# Sheet1.net
KiCad netlist of a schematic drawn in Altium Designer
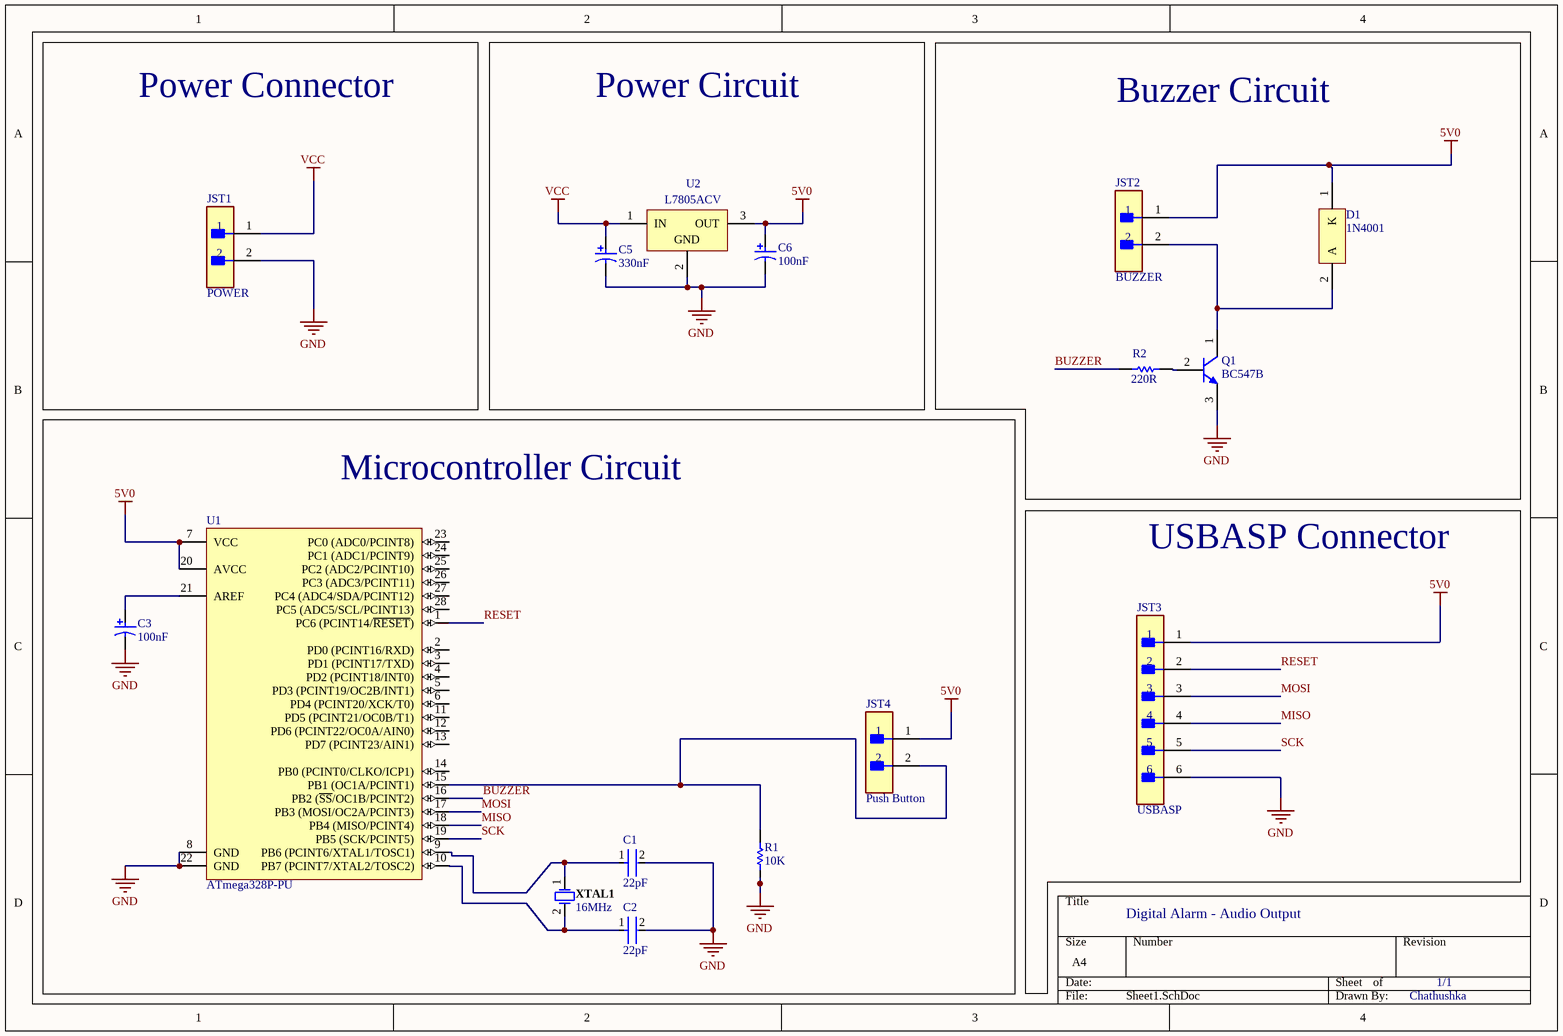
[diagram p0: Sheet1.SchDoc]

(export (version "E")
  (design (tool "Eeschema 10.0.6"))
  (components
    (comp (ref "C1")
      (value "22pF")
      (footprint "FP-RCE0K1-MFG")
      (description "Cap Ceramic 22pF 50V C0G ±5% Radial 5mm +125°C Automotive Bulk")
      (fields (field (name "TOLERANCE") "5%"))
      (libsource (lib "Altium Content Vault") (part "b4654b650e69147ec39a6b967a45e02"))
    )
    (comp (ref "C2")
      (value "22pF")
      (footprint "FP-RCE0K1-MFG")
      (description "Cap Ceramic 22pF 50V C0G ±5% Radial 5mm +125°C Automotive Bulk")
      (fields (field (name "TOLERANCE") "5%"))
      (libsource (lib "Altium Content Vault") (part "b4654b650e69147ec39a6b967a45e02"))
    )
    (comp (ref "C3")
      (value "100nF")
      (footprint "CAPPR65-350-1150X800X1250")
      (description "Aluminum Electrolytic Capacitor, 100 uF, +/- 20%, 50 V, -40 to 85 degC, 2-Pin THD, RoHS, Bulk")
      (fields (field (name "MANUFACTURER") "Panasonic") (field (name "VOLTAGE") "50V"))
      (libsource (lib "Altium Content Vault") (part "CAP-P-2"))
    )
    (comp (ref "C5")
      (value "330nF")
      (footprint "CAPPR65-350-1150X800X1250")
      (description "Aluminum Electrolytic Capacitor, 100 nF, +/- 20%, 50 V, -40 to 85 degC, 2-Pin THD, RoHS, Bulk")
      (fields (field (name "MANUFACTURER") "Panasonic") (field (name "VOLTAGE") "50V"))
      (libsource (lib "Altium Content Vault") (part "CAP-P-2"))
    )
    (comp (ref "C6")
      (value "100nF")
      (footprint "CAPPR65-350-1150X800X1250")
      (description "Aluminum Electrolytic Capacitor, 100 nF, +/- 20%, 50 V, -40 to 85 degC, 2-Pin THD, RoHS, Bulk")
      (fields (field (name "MANUFACTURER") "Panasonic") (field (name "VOLTAGE") "50V"))
      (libsource (lib "Altium Content Vault") (part "CAP-P-2"))
    )
    (comp (ref "D1")
      (value "1N4001")
      (footprint "ONSC-AXIAL_LEAD-2-59-10_P")
      (description "Standard Recovery Rectifier, 2-Pin Axial_Lead, Pb-Free, Bulk Bag")
      (fields (field (name "MANUFACTURER") "On Semiconductor"))
      (libsource (lib "Altium Content Vault") (part "ONSC-D-K1A2-2_A"))
    )
    (comp (ref "JST1")
      (value "POWER")
      (footprint "FP-B2B-XH-A_LF_SN-MFG")
      (description "CONN HEADER VERT 2POS 2.5MM")
      (libsource (lib "Altium Content Vault") (part "3bc925449376181038e59eaffc5286c"))
    )
    (comp (ref "JST2")
      (value "BUZZER")
      (footprint "FP-B2B-XH-A_LF_SN-MFG")
      (description "CONN HEADER VERT 2POS 2.5MM")
      (libsource (lib "Altium Content Vault") (part "3bc925449376181038e59eaffc5286c"))
    )
    (comp (ref "JST3")
      (value "USBASP")
      (footprint "FP-M30-6100646-MFG")
      (description "CONN HEADER VERT 6POS 1.25MM")
      (fields (field (name "MANUFACTURER PART NUMBER") "M30-6100646") (field (name "MANUFACTURER") "Harwin"))
      (libsource (lib "Altium Content Vault") (part "f2cb566baf1c37ab5a3b8e90bbeafd6"))
    )
    (comp (ref "JST4")
      (value "Push Button")
      (footprint "FP-B2B-XH-A_LF_SN-MFG")
      (description "CONN HEADER VERT 2POS 2.5MM")
      (libsource (lib "Altium Content Vault") (part "3bc925449376181038e59eaffc5286c"))
    )
    (comp (ref "Q1")
      (value "BC547B")
      (footprint "ONSC-TO-92-3-29-11")
      (description "Amplifier Transistor, NPN Silicon, 3-Pin TO-92, Bulk Box")
      (fields (field (name "MANUFACTURER") "On Semiconductor"))
      (libsource (lib "Altium Content Vault") (part "ONSC-NPN-C1B2E3-3"))
    )
    (comp (ref "R1")
      (value "10K")
      (footprint "OMTE-RES7X2.5-2")
      (fields
        (field (name "TOLERANCE") "±5%")
        (field (name "PARTNUMBER") "OD103JE")
        (field (name "MANUFACTURER") "Ohmite")
      )
      (libsource (lib "Altium Content Vault") (part "RES-2"))
    )
    (comp (ref "R2")
      (value "220R")
      (footprint "OMTE-RES7X2.5-2")
      (fields
        (field (name "TOLERANCE") "±5%")
        (field (name "PARTNUMBER") "OD103JE")
        (field (name "MANUFACTURER") "Ohmite")
      )
      (libsource (lib "Altium Content Vault") (part "RES-2"))
    )
    (comp (ref "U1")
      (value "ATmega328P-PU")
      (footprint "28P3")
      (libsource (lib "Altium Content Vault") (part "MC-8B-ATM48-IL28"))
    )
    (comp (ref "U2")
      (value "L7805ACV")
      (footprint "TO220")
      (description "Positive Voltage Regulator, 5V, 3-Pin TO-220")
      (libsource (lib "Altium Content Vault") (part "PM-REG-L4940-SIL3"))
    )
    (comp (ref "XTAL1")
      (value "16MHz")
      (footprint "FOX-FOXSLF160-20")
      (description "Resistance Weld Thru-Hole Crystal, 16 MHz, -20 to 70 degC, 2-Pin THD, RoHS, Bulk")
      (fields (field (name "TOLERANCE") "1%"))
      (libsource (lib "Altium Content Vault") (part "XTAL-1-2-2"))
    )
  )
  (nets
    (net (code "1") (name "/BUZZER") (class "Default")
      (node (ref "R2") (pin "1") (pinfunction "1_1") (pintype "passive"))
      (node (ref "U1") (pin "16") (pinfunction "PB2_(~{SS}/OC1B/PCINT2)_16") (pintype "bidirectional"))
    )
    (net (code "2") (name "/MISO") (class "Default")
      (node (ref "JST3") (pin "4") (pinfunction "4_4") (pintype "passive"))
      (node (ref "U1") (pin "18") (pinfunction "PB4_(MISO/PCINT4)_18") (pintype "bidirectional"))
    )
    (net (code "3") (name "/MOSI") (class "Default")
      (node (ref "JST3") (pin "3") (pinfunction "3_3") (pintype "passive"))
      (node (ref "U1") (pin "17") (pinfunction "PB3_(MOSI/OC2A/PCINT3)_17") (pintype "bidirectional"))
    )
    (net (code "4") (name "/RESET") (class "Default")
      (node (ref "JST3") (pin "2") (pinfunction "2_2") (pintype "passive"))
      (node (ref "U1") (pin "1") (pinfunction "PC6_(PCINT14/~{RESET})_1") (pintype "bidirectional"))
    )
    (net (code "5") (name "/SCK") (class "Default")
      (node (ref "JST3") (pin "5") (pinfunction "5_5") (pintype "passive"))
      (node (ref "U1") (pin "19") (pinfunction "PB5_(SCK/PCINT5)_19") (pintype "bidirectional"))
    )
    (net (code "6") (name "5V0") (class "Default")
      (node (ref "C6") (pin "1") (pinfunction "1_1") (pintype "passive"))
      (node (ref "D1") (pin "1") (pinfunction "K_1") (pintype "passive"))
      (node (ref "JST2") (pin "1") (pinfunction "1_1") (pintype "passive"))
      (node (ref "JST3") (pin "1") (pinfunction "1_1") (pintype "passive"))
      (node (ref "JST4") (pin "1") (pinfunction "1_1") (pintype "passive"))
      (node (ref "U1") (pin "20") (pinfunction "AVCC_20") (pintype "power_in"))
      (node (ref "U1") (pin "7") (pinfunction "VCC_7") (pintype "power_in"))
      (node (ref "U2") (pin "3") (pinfunction "OUT_3") (pintype "power_in"))
    )
    (net (code "7") (name "GND") (class "Default")
      (node (ref "C1") (pin "2") (pinfunction "2_2") (pintype "passive"))
      (node (ref "C2") (pin "2") (pinfunction "2_2") (pintype "passive"))
      (node (ref "C3") (pin "2") (pinfunction "2_2") (pintype "passive"))
      (node (ref "C5") (pin "2") (pinfunction "2_2") (pintype "passive"))
      (node (ref "C6") (pin "2") (pinfunction "2_2") (pintype "passive"))
      (node (ref "JST1") (pin "2") (pinfunction "2_2") (pintype "passive"))
      (node (ref "JST3") (pin "6") (pinfunction "6_6") (pintype "passive"))
      (node (ref "Q1") (pin "3") (pinfunction "E_3") (pintype "passive"))
      (node (ref "R1") (pin "2") (pinfunction "2_2") (pintype "passive"))
      (node (ref "U1") (pin "22") (pinfunction "GND_22") (pintype "power_in"))
      (node (ref "U1") (pin "8") (pinfunction "GND_8") (pintype "power_in"))
      (node (ref "U2") (pin "2") (pinfunction "GND_2") (pintype "power_in"))
    )
    (net (code "8") (name "Net-(D1-A)") (class "Default")
      (node (ref "D1") (pin "2") (pinfunction "A_2") (pintype "passive"))
      (node (ref "JST2") (pin "2") (pinfunction "2_2") (pintype "passive"))
      (node (ref "Q1") (pin "1") (pinfunction "C_1") (pintype "passive"))
    )
    (net (code "9") (name "Net-(Q1-B)") (class "Default")
      (node (ref "Q1") (pin "2") (pinfunction "B_2") (pintype "passive"))
      (node (ref "R2") (pin "2") (pinfunction "2_2") (pintype "passive"))
    )
    (net (code "10") (name "Net-(U1-AREF)") (class "Default")
      (node (ref "C3") (pin "1") (pinfunction "1_1") (pintype "passive"))
      (node (ref "U1") (pin "21") (pinfunction "AREF_21") (pintype "power_in"))
    )
    (net (code "11") (name "Net-(U1-PB1_(OC1A{slash}PCINT1))") (class "Default")
      (node (ref "JST4") (pin "2") (pinfunction "2_2") (pintype "passive"))
      (node (ref "R1") (pin "1") (pinfunction "1_1") (pintype "passive"))
      (node (ref "U1") (pin "15") (pinfunction "PB1_(OC1A/PCINT1)_15") (pintype "bidirectional"))
    )
    (net (code "12") (name "Net-(U1-PB6_(PCINT6{slash}XTAL1{slash}TOSC1))") (class "Default")
      (node (ref "C1") (pin "1") (pinfunction "1_1") (pintype "passive"))
      (node (ref "U1") (pin "9") (pinfunction "PB6_(PCINT6/XTAL1/TOSC1)_9") (pintype "bidirectional"))
      (node (ref "XTAL1") (pin "1") (pinfunction "1_1") (pintype "passive"))
    )
    (net (code "13") (name "Net-(U1-PB7_(PCINT7{slash}XTAL2{slash}TOSC2))") (class "Default")
      (node (ref "C2") (pin "1") (pinfunction "1_1") (pintype "passive"))
      (node (ref "U1") (pin "10") (pinfunction "PB7_(PCINT7/XTAL2/TOSC2)_10") (pintype "bidirectional"))
      (node (ref "XTAL1") (pin "2") (pinfunction "2_2") (pintype "passive"))
    )
    (net (code "14") (name "VCC") (class "Default")
      (node (ref "C5") (pin "1") (pinfunction "1_1") (pintype "passive"))
      (node (ref "JST1") (pin "1") (pinfunction "1_1") (pintype "passive"))
      (node (ref "U2") (pin "1") (pinfunction "IN_1") (pintype "power_in"))
    )
    (net (code "15") (name "unconnected-(U1-PB0_(PCINT0{slash}CLKO{slash}ICP1)-Pad14)") (class "Default")
      (node (ref "U1") (pin "14") (pinfunction "PB0_(PCINT0/CLKO/ICP1)_14") (pintype "bidirectional"))
    )
    (net (code "16") (name "unconnected-(U1-PC0_(ADC0{slash}PCINT8)-Pad23)") (class "Default")
      (node (ref "U1") (pin "23") (pinfunction "PC0_(ADC0/PCINT8)_23") (pintype "bidirectional"))
    )
    (net (code "17") (name "unconnected-(U1-PC1_(ADC1{slash}PCINT9)-Pad24)") (class "Default")
      (node (ref "U1") (pin "24") (pinfunction "PC1_(ADC1/PCINT9)_24") (pintype "bidirectional"))
    )
    (net (code "18") (name "unconnected-(U1-PC2_(ADC2{slash}PCINT10)-Pad25)") (class "Default")
      (node (ref "U1") (pin "25") (pinfunction "PC2_(ADC2/PCINT10)_25") (pintype "bidirectional"))
    )
    (net (code "19") (name "unconnected-(U1-PC3_(ADC3{slash}PCINT11)-Pad26)") (class "Default")
      (node (ref "U1") (pin "26") (pinfunction "PC3_(ADC3/PCINT11)_26") (pintype "bidirectional"))
    )
    (net (code "20") (name "unconnected-(U1-PC4_(ADC4{slash}SDA{slash}PCINT12)-Pad27)") (class "Default")
      (node (ref "U1") (pin "27") (pinfunction "PC4_(ADC4/SDA/PCINT12)_27") (pintype "bidirectional"))
    )
    (net (code "21") (name "unconnected-(U1-PC5_(ADC5{slash}SCL{slash}PCINT13)-Pad28)") (class "Default")
      (node (ref "U1") (pin "28") (pinfunction "PC5_(ADC5/SCL/PCINT13)_28") (pintype "bidirectional"))
    )
    (net (code "22") (name "unconnected-(U1-PD0_(PCINT16{slash}RXD)-Pad2)") (class "Default")
      (node (ref "U1") (pin "2") (pinfunction "PD0_(PCINT16/RXD)_2") (pintype "bidirectional"))
    )
    (net (code "23") (name "unconnected-(U1-PD1_(PCINT17{slash}TXD)-Pad3)") (class "Default")
      (node (ref "U1") (pin "3") (pinfunction "PD1_(PCINT17/TXD)_3") (pintype "bidirectional"))
    )
    (net (code "24") (name "unconnected-(U1-PD2_(PCINT18{slash}INT0)-Pad4)") (class "Default")
      (node (ref "U1") (pin "4") (pinfunction "PD2_(PCINT18/INT0)_4") (pintype "bidirectional"))
    )
    (net (code "25") (name "unconnected-(U1-PD3_(PCINT19{slash}OC2B{slash}INT1)-Pad5)") (class "Default")
      (node (ref "U1") (pin "5") (pinfunction "PD3_(PCINT19/OC2B/INT1)_5") (pintype "bidirectional"))
    )
    (net (code "26") (name "unconnected-(U1-PD4_(PCINT20{slash}XCK{slash}T0)-Pad6)") (class "Default")
      (node (ref "U1") (pin "6") (pinfunction "PD4_(PCINT20/XCK/T0)_6") (pintype "bidirectional"))
    )
    (net (code "27") (name "unconnected-(U1-PD5_(PCINT21{slash}OC0B{slash}T1)-Pad11)") (class "Default")
      (node (ref "U1") (pin "11") (pinfunction "PD5_(PCINT21/OC0B/T1)_11") (pintype "bidirectional"))
    )
    (net (code "28") (name "unconnected-(U1-PD6_(PCINT22{slash}OC0A{slash}AIN0)-Pad12)") (class "Default")
      (node (ref "U1") (pin "12") (pinfunction "PD6_(PCINT22/OC0A/AIN0)_12") (pintype "bidirectional"))
    )
    (net (code "29") (name "unconnected-(U1-PD7_(PCINT23{slash}AIN1)-Pad13)") (class "Default")
      (node (ref "U1") (pin "13") (pinfunction "PD7_(PCINT23/AIN1)_13") (pintype "bidirectional"))
    )
  )
)
